# design.net
KiCad netlist of a schematic drawn in Altium Designer
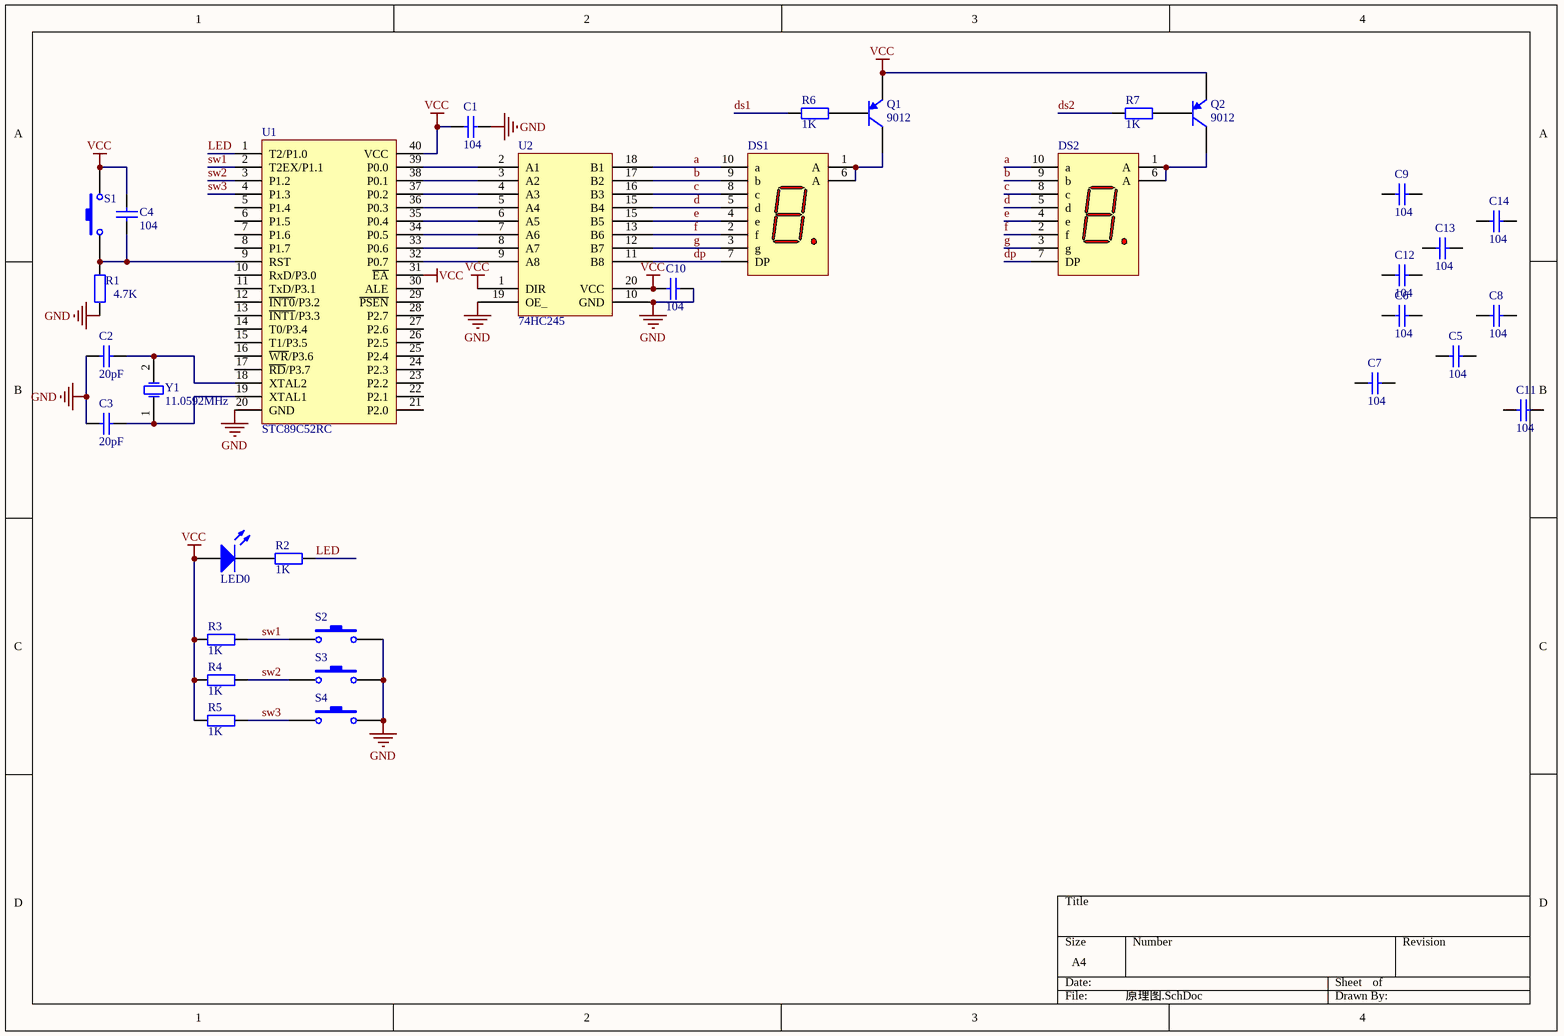
[diagram p0: 原理图.SchDoc]

(export (version "E")
  (design (tool "Eeschema 10.0.6"))
  (components
    (comp (ref "C1")
      (value "104")
      (footprint "RAD-0.3")
      (description "Capacitor")
      (fields (field (name "Comment") "Cap") (field (name "PUBLISHER") "Altium Limited"))
      (libsource (lib "Miscellaneous Devices") (part "Cap"))
    )
    (comp (ref "C2")
      (value "20pF")
      (footprint "RAD-0.3")
      (description "Capacitor")
      (fields (field (name "Comment") "Cap") (field (name "PUBLISHER") "Altium Limited"))
      (libsource (lib "Miscellaneous Devices") (part "Cap"))
    )
    (comp (ref "C3")
      (value "20pF")
      (footprint "RAD-0.3")
      (description "Capacitor")
      (fields (field (name "Comment") "Cap") (field (name "PUBLISHER") "Altium Limited"))
      (libsource (lib "Miscellaneous Devices") (part "Cap"))
    )
    (comp (ref "C4")
      (value "104")
      (footprint "RAD-0.3")
      (description "Capacitor")
      (fields (field (name "Comment") "Cap") (field (name "PUBLISHER") "Altium Limited"))
      (libsource (lib "Miscellaneous Devices") (part "Cap"))
    )
    (comp (ref "C5")
      (value "104")
      (footprint "RAD-0.3")
      (description "Capacitor")
      (fields (field (name "Comment") "Cap") (field (name "PUBLISHER") "Altium Limited"))
      (libsource (lib "Miscellaneous Devices") (part "Cap"))
    )
    (comp (ref "C6")
      (value "104")
      (footprint "RAD-0.3")
      (description "Capacitor")
      (fields (field (name "Comment") "Cap") (field (name "PUBLISHER") "Altium Limited"))
      (libsource (lib "Miscellaneous Devices") (part "Cap"))
    )
    (comp (ref "C7")
      (value "104")
      (footprint "RAD-0.3")
      (description "Capacitor")
      (fields (field (name "Comment") "Cap") (field (name "PUBLISHER") "Altium Limited"))
      (libsource (lib "Miscellaneous Devices") (part "Cap"))
    )
    (comp (ref "C8")
      (value "104")
      (footprint "RAD-0.3")
      (description "Capacitor")
      (fields (field (name "Comment") "Cap") (field (name "PUBLISHER") "Altium Limited"))
      (libsource (lib "Miscellaneous Devices") (part "Cap"))
    )
    (comp (ref "C9")
      (value "104")
      (footprint "RAD-0.3")
      (description "Capacitor")
      (fields (field (name "Comment") "Cap") (field (name "PUBLISHER") "Altium Limited"))
      (libsource (lib "Miscellaneous Devices") (part "Cap"))
    )
    (comp (ref "C10")
      (value "104")
      (footprint "RAD-0.3")
      (description "Capacitor")
      (fields (field (name "Comment") "Cap") (field (name "PUBLISHER") "Altium Limited"))
      (libsource (lib "Miscellaneous Devices") (part "Cap"))
    )
    (comp (ref "C11")
      (value "104")
      (footprint "RAD-0.3")
      (description "Capacitor")
      (fields (field (name "Comment") "Cap") (field (name "PUBLISHER") "Altium Limited"))
      (libsource (lib "Miscellaneous Devices") (part "Cap"))
    )
    (comp (ref "C12")
      (value "104")
      (footprint "RAD-0.3")
      (description "Capacitor")
      (fields (field (name "Comment") "Cap") (field (name "PUBLISHER") "Altium Limited"))
      (libsource (lib "Miscellaneous Devices") (part "Cap"))
    )
    (comp (ref "C13")
      (value "104")
      (footprint "RAD-0.3")
      (description "Capacitor")
      (fields (field (name "Comment") "Cap") (field (name "PUBLISHER") "Altium Limited"))
      (libsource (lib "Miscellaneous Devices") (part "Cap"))
    )
    (comp (ref "C14")
      (value "104")
      (footprint "RAD-0.3")
      (description "Capacitor")
      (fields (field (name "Comment") "Cap") (field (name "PUBLISHER") "Altium Limited"))
      (libsource (lib "Miscellaneous Devices") (part "Cap"))
    )
    (comp (ref "D1")
      (value "LED0")
      (footprint "LED-0")
      (description "Typical INFRARED GaAs LED")
      (fields (field (name "PUBLISHER") "Altium Limited"))
      (libsource (lib "Miscellaneous Devices") (part "LED0"))
    )
    (comp (ref "DS1")
      (value "Dpy Red-CA")
      (footprint "A")
      (description "7.62 mm Black Surface HER 7-Segment Display: CA, RH DP")
      (fields (field (name "PUBLISHER") "Altium Limited"))
      (libsource (lib "Miscellaneous Devices") (part "Dpy Red-CA"))
    )
    (comp (ref "DS2")
      (value "Dpy Red-CA")
      (footprint "A")
      (description "7.62 mm Black Surface HER 7-Segment Display: CA, RH DP")
      (fields (field (name "PUBLISHER") "Altium Limited"))
      (libsource (lib "Miscellaneous Devices") (part "Dpy Red-CA"))
    )
    (comp (ref "Q1")
      (value "9012")
      (footprint "SOT-23B_N")
      (description "PNP Bipolar Transistor")
      (fields (field (name "PUBLISHER") "Altium Limited"))
      (libsource (lib "Miscellaneous Devices") (part "PNP"))
    )
    (comp (ref "Q2")
      (value "9012")
      (footprint "SOT-23B_N")
      (description "PNP Bipolar Transistor")
      (fields (field (name "PUBLISHER") "Altium Limited"))
      (libsource (lib "Miscellaneous Devices") (part "PNP"))
    )
    (comp (ref "R1")
      (value "4.7K")
      (footprint "AXIAL-0.4")
      (description "Resistor")
      (fields (field (name "Comment") "Res2") (field (name "PUBLISHER") "Altium Limited"))
      (libsource (lib "") (part "Res2_1"))
    )
    (comp (ref "R2")
      (value "1K")
      (footprint "AXIAL-0.4")
      (description "Resistor")
      (fields (field (name "Comment") "Res2") (field (name "PUBLISHER") "Altium Limited"))
      (libsource (lib "Miscellaneous Devices") (part "Res2"))
    )
    (comp (ref "R3")
      (value "1K")
      (footprint "AXIAL-0.4")
      (description "Resistor")
      (fields (field (name "Comment") "Res2") (field (name "PUBLISHER") "Altium Limited"))
      (libsource (lib "Miscellaneous Devices") (part "Res2"))
    )
    (comp (ref "R4")
      (value "1K")
      (footprint "AXIAL-0.4")
      (description "Resistor")
      (fields (field (name "Comment") "Res2") (field (name "PUBLISHER") "Altium Limited"))
      (libsource (lib "Miscellaneous Devices") (part "Res2"))
    )
    (comp (ref "R5")
      (value "1K")
      (footprint "AXIAL-0.4")
      (description "Resistor")
      (fields (field (name "Comment") "Res2") (field (name "PUBLISHER") "Altium Limited"))
      (libsource (lib "Miscellaneous Devices") (part "Res2"))
    )
    (comp (ref "R6")
      (value "1K")
      (footprint "AXIAL-0.4")
      (description "Resistor")
      (fields (field (name "Comment") "Res2") (field (name "PUBLISHER") "Altium Limited"))
      (libsource (lib "Miscellaneous Devices") (part "Res2"))
    )
    (comp (ref "R7")
      (value "1K")
      (footprint "AXIAL-0.4")
      (description "Resistor")
      (fields (field (name "Comment") "Res2") (field (name "PUBLISHER") "Altium Limited"))
      (libsource (lib "Miscellaneous Devices") (part "Res2"))
    )
    (comp (ref "S1")
      (value "SW-PB")
      (footprint "SPST-2")
      (description "Switch")
      (fields (field (name "PUBLISHER") "Altium Limited"))
      (libsource (lib "Miscellaneous Devices") (part "SW-PB"))
    )
    (comp (ref "S2")
      (value "SW-PB")
      (footprint "SPST-2")
      (description "Switch")
      (fields (field (name "PUBLISHER") "Altium Limited"))
      (libsource (lib "Miscellaneous Devices") (part "SW-PB"))
    )
    (comp (ref "S3")
      (value "SW-PB")
      (footprint "SPST-2")
      (description "Switch")
      (fields (field (name "PUBLISHER") "Altium Limited"))
      (libsource (lib "Miscellaneous Devices") (part "SW-PB"))
    )
    (comp (ref "S4")
      (value "SW-PB")
      (footprint "SPST-2")
      (description "Switch")
      (fields (field (name "PUBLISHER") "Altium Limited"))
      (libsource (lib "Miscellaneous Devices") (part "SW-PB"))
    )
    (comp (ref "U1")
      (value "STC89C52RC")
      (footprint "DIP40-600")
      (description "STC单片机")
      (libsource (lib "2.3   - STC系列单片机") (part "STC89C52RC"))
    )
    (comp (ref "U2") (value "74HC245") (libsource (lib "1.2   - 74系列芯片") (part "74HC245")))
    (comp (ref "Y1")
      (value "11.0592MHz")
      (footprint "R38")
      (description "Crystal Oscillator")
      (fields (field (name "PUBLISHER") "Altium Limited"))
      (libsource (lib "Miscellaneous Devices") (part "XTAL"))
    )
  )
  (nets
    (net (code "1") (name "/LED") (class "Default")
      (node (ref "R2") (pin "2") (pinfunction "2_2") (pintype "passive"))
      (node (ref "U1") (pin "1") (pinfunction "T2/P1.0_1") (pintype "passive"))
    )
    (net (code "2") (name "/a") (class "Default")
      (node (ref "DS1") (pin "10") (pinfunction "a_10") (pintype "passive"))
      (node (ref "DS2") (pin "10") (pinfunction "a_10") (pintype "passive"))
      (node (ref "U2") (pin "18") (pinfunction "B1_18") (pintype "passive"))
    )
    (net (code "3") (name "/b") (class "Default")
      (node (ref "DS1") (pin "9") (pinfunction "b_9") (pintype "passive"))
      (node (ref "DS2") (pin "9") (pinfunction "b_9") (pintype "passive"))
      (node (ref "U2") (pin "17") (pinfunction "B2_17") (pintype "passive"))
    )
    (net (code "4") (name "/c") (class "Default")
      (node (ref "DS1") (pin "8") (pinfunction "c_8") (pintype "passive"))
      (node (ref "DS2") (pin "8") (pinfunction "c_8") (pintype "passive"))
      (node (ref "U2") (pin "16") (pinfunction "B3_16") (pintype "passive"))
    )
    (net (code "5") (name "/d") (class "Default")
      (node (ref "DS1") (pin "5") (pinfunction "d_5") (pintype "passive"))
      (node (ref "DS2") (pin "5") (pinfunction "d_5") (pintype "passive"))
      (node (ref "U2") (pin "15") (pinfunction "B4_15") (pintype "passive"))
    )
    (net (code "6") (name "/dp") (class "Default")
      (node (ref "DS1") (pin "7") (pinfunction "DP_7") (pintype "passive"))
      (node (ref "DS2") (pin "7") (pinfunction "DP_7") (pintype "passive"))
      (node (ref "U2") (pin "11") (pinfunction "B8_11") (pintype "passive"))
    )
    (net (code "7") (name "/ds1") (class "Default")
      (node (ref "R6") (pin "1") (pinfunction "1_1") (pintype "passive"))
    )
    (net (code "8") (name "/ds2") (class "Default")
      (node (ref "R7") (pin "1") (pinfunction "1_1") (pintype "passive"))
    )
    (net (code "9") (name "/e") (class "Default")
      (node (ref "DS1") (pin "4") (pinfunction "e_4") (pintype "passive"))
      (node (ref "DS2") (pin "4") (pinfunction "e_4") (pintype "passive"))
      (node (ref "U2") (pin "15") (pinfunction "B5_15") (pintype "passive"))
    )
    (net (code "10") (name "/f") (class "Default")
      (node (ref "DS1") (pin "2") (pinfunction "f_2") (pintype "passive"))
      (node (ref "DS2") (pin "2") (pinfunction "f_2") (pintype "passive"))
      (node (ref "U2") (pin "13") (pinfunction "B6_13") (pintype "passive"))
    )
    (net (code "11") (name "/g") (class "Default")
      (node (ref "DS1") (pin "3") (pinfunction "g_3") (pintype "passive"))
      (node (ref "DS2") (pin "3") (pinfunction "g_3") (pintype "passive"))
      (node (ref "U2") (pin "12") (pinfunction "B7_12") (pintype "passive"))
    )
    (net (code "12") (name "/sw1") (class "Default")
      (node (ref "R3") (pin "2") (pinfunction "2_2") (pintype "passive"))
      (node (ref "S2") (pin "1") (pinfunction "1_1") (pintype "passive"))
      (node (ref "U1") (pin "2") (pinfunction "T2EX/P1.1_2") (pintype "passive"))
    )
    (net (code "13") (name "/sw2") (class "Default")
      (node (ref "R4") (pin "2") (pinfunction "2_2") (pintype "passive"))
      (node (ref "S3") (pin "1") (pinfunction "1_1") (pintype "passive"))
      (node (ref "U1") (pin "3") (pinfunction "P1.2_3") (pintype "passive"))
    )
    (net (code "14") (name "/sw3") (class "Default")
      (node (ref "R5") (pin "2") (pinfunction "2_2") (pintype "passive"))
      (node (ref "S4") (pin "1") (pinfunction "1_1") (pintype "passive"))
      (node (ref "U1") (pin "4") (pinfunction "P1.3_4") (pintype "passive"))
    )
    (net (code "15") (name "GND") (class "Default")
      (node (ref "C1") (pin "2") (pinfunction "2_2") (pintype "passive"))
      (node (ref "C10") (pin "2") (pinfunction "2_2") (pintype "passive"))
      (node (ref "C2") (pin "1") (pinfunction "1_1") (pintype "passive"))
      (node (ref "C3") (pin "1") (pinfunction "1_1") (pintype "passive"))
      (node (ref "R1") (pin "1") (pinfunction "1_1") (pintype "passive"))
      (node (ref "S2") (pin "2") (pinfunction "2_2") (pintype "passive"))
      (node (ref "S3") (pin "2") (pinfunction "2_2") (pintype "passive"))
      (node (ref "S4") (pin "2") (pinfunction "2_2") (pintype "passive"))
      (node (ref "U1") (pin "20") (pinfunction "GND_20") (pintype "passive"))
      (node (ref "U2") (pin "10") (pinfunction "GND_10") (pintype "passive"))
      (node (ref "U2") (pin "19") (pinfunction "OE__19") (pintype "passive"))
    )
    (net (code "16") (name "Net-(D1-K)") (class "Default")
      (node (ref "D1") (pin "2") (pinfunction "K_2") (pintype "passive"))
      (node (ref "R2") (pin "1") (pinfunction "1_1") (pintype "passive"))
    )
    (net (code "17") (name "Net-(Q1-B)") (class "Default")
      (node (ref "Q1") (pin "2") (pinfunction "B_2") (pintype "passive"))
      (node (ref "R6") (pin "2") (pinfunction "2_2") (pintype "passive"))
    )
    (net (code "18") (name "Net-(Q1-C)") (class "Default")
      (node (ref "DS1") (pin "1") (pinfunction "A_1") (pintype "passive"))
      (node (ref "DS1") (pin "6") (pinfunction "A_6") (pintype "passive"))
      (node (ref "Q1") (pin "1") (pinfunction "C_1") (pintype "passive"))
    )
    (net (code "19") (name "Net-(Q2-B)") (class "Default")
      (node (ref "Q2") (pin "2") (pinfunction "B_2") (pintype "passive"))
      (node (ref "R7") (pin "2") (pinfunction "2_2") (pintype "passive"))
    )
    (net (code "20") (name "Net-(Q2-C)") (class "Default")
      (node (ref "DS2") (pin "1") (pinfunction "A_1") (pintype "passive"))
      (node (ref "DS2") (pin "6") (pinfunction "A_6") (pintype "passive"))
      (node (ref "Q2") (pin "1") (pinfunction "C_1") (pintype "passive"))
    )
    (net (code "21") (name "Net-(U1-P0.0)") (class "Default")
      (node (ref "U1") (pin "39") (pinfunction "P0.0_39") (pintype "passive"))
      (node (ref "U2") (pin "2") (pinfunction "A1_2") (pintype "passive"))
    )
    (net (code "22") (name "Net-(U1-P0.1)") (class "Default")
      (node (ref "U1") (pin "38") (pinfunction "P0.1_38") (pintype "passive"))
      (node (ref "U2") (pin "3") (pinfunction "A2_3") (pintype "passive"))
    )
    (net (code "23") (name "Net-(U1-P0.2)") (class "Default")
      (node (ref "U1") (pin "37") (pinfunction "P0.2_37") (pintype "passive"))
      (node (ref "U2") (pin "4") (pinfunction "A3_4") (pintype "passive"))
    )
    (net (code "24") (name "Net-(U1-P0.3)") (class "Default")
      (node (ref "U1") (pin "36") (pinfunction "P0.3_36") (pintype "passive"))
      (node (ref "U2") (pin "5") (pinfunction "A4_5") (pintype "passive"))
    )
    (net (code "25") (name "Net-(U1-P0.4)") (class "Default")
      (node (ref "U1") (pin "35") (pinfunction "P0.4_35") (pintype "passive"))
      (node (ref "U2") (pin "6") (pinfunction "A5_6") (pintype "passive"))
    )
    (net (code "26") (name "Net-(U1-P0.5)") (class "Default")
      (node (ref "U1") (pin "34") (pinfunction "P0.5_34") (pintype "passive"))
      (node (ref "U2") (pin "7") (pinfunction "A6_7") (pintype "passive"))
    )
    (net (code "27") (name "Net-(U1-P0.6)") (class "Default")
      (node (ref "U1") (pin "33") (pinfunction "P0.6_33") (pintype "passive"))
      (node (ref "U2") (pin "8") (pinfunction "A7_8") (pintype "passive"))
    )
    (net (code "28") (name "Net-(U1-P0.7)") (class "Default")
      (node (ref "U1") (pin "32") (pinfunction "P0.7_32") (pintype "passive"))
      (node (ref "U2") (pin "9") (pinfunction "A8_9") (pintype "passive"))
    )
    (net (code "29") (name "Net-(U1-RST)") (class "Default")
      (node (ref "C4") (pin "1") (pinfunction "1_1") (pintype "passive"))
      (node (ref "R1") (pin "2") (pinfunction "2_2") (pintype "passive"))
      (node (ref "S1") (pin "1") (pinfunction "1_1") (pintype "passive"))
      (node (ref "U1") (pin "9") (pinfunction "RST_9") (pintype "passive"))
    )
    (net (code "30") (name "Net-(U1-XTAL1)") (class "Default")
      (node (ref "C3") (pin "2") (pinfunction "2_2") (pintype "passive"))
      (node (ref "U1") (pin "19") (pinfunction "XTAL1_19") (pintype "passive"))
      (node (ref "Y1") (pin "1") (pinfunction "OSC1_1") (pintype "passive"))
    )
    (net (code "31") (name "Net-(U1-XTAL2)") (class "Default")
      (node (ref "C2") (pin "2") (pinfunction "2_2") (pintype "passive"))
      (node (ref "U1") (pin "18") (pinfunction "XTAL2_18") (pintype "passive"))
      (node (ref "Y1") (pin "2") (pinfunction "OSC2_2") (pintype "passive"))
    )
    (net (code "32") (name "VCC") (class "Default")
      (node (ref "C1") (pin "1") (pinfunction "1_1") (pintype "passive"))
      (node (ref "C10") (pin "1") (pinfunction "1_1") (pintype "passive"))
      (node (ref "C4") (pin "2") (pinfunction "2_2") (pintype "passive"))
      (node (ref "D1") (pin "1") (pinfunction "A_1") (pintype "passive"))
      (node (ref "Q1") (pin "3") (pinfunction "E_3") (pintype "passive"))
      (node (ref "Q2") (pin "3") (pinfunction "E_3") (pintype "passive"))
      (node (ref "R3") (pin "1") (pinfunction "1_1") (pintype "passive"))
      (node (ref "R4") (pin "1") (pinfunction "1_1") (pintype "passive"))
      (node (ref "R5") (pin "1") (pinfunction "1_1") (pintype "passive"))
      (node (ref "S1") (pin "2") (pinfunction "2_2") (pintype "passive"))
      (node (ref "U1") (pin "31") (pinfunction "~{EA}_31") (pintype "passive"))
      (node (ref "U1") (pin "40") (pinfunction "VCC_40") (pintype "passive"))
      (node (ref "U2") (pin "1") (pinfunction "DIR_1") (pintype "passive"))
      (node (ref "U2") (pin "20") (pinfunction "VCC_20") (pintype "passive"))
    )
    (net (code "33") (name "unconnected-(C5-Pad1)") (class "Default")
      (node (ref "C5") (pin "1") (pinfunction "1_1") (pintype "passive"))
    )
    (net (code "34") (name "unconnected-(C5-Pad2)") (class "Default")
      (node (ref "C5") (pin "2") (pinfunction "2_2") (pintype "passive"))
    )
    (net (code "35") (name "unconnected-(C6-Pad1)") (class "Default")
      (node (ref "C6") (pin "1") (pinfunction "1_1") (pintype "passive"))
    )
    (net (code "36") (name "unconnected-(C6-Pad2)") (class "Default")
      (node (ref "C6") (pin "2") (pinfunction "2_2") (pintype "passive"))
    )
    (net (code "37") (name "unconnected-(C7-Pad1)") (class "Default")
      (node (ref "C7") (pin "1") (pinfunction "1_1") (pintype "passive"))
    )
    (net (code "38") (name "unconnected-(C7-Pad2)") (class "Default")
      (node (ref "C7") (pin "2") (pinfunction "2_2") (pintype "passive"))
    )
    (net (code "39") (name "unconnected-(C8-Pad1)") (class "Default")
      (node (ref "C8") (pin "1") (pinfunction "1_1") (pintype "passive"))
    )
    (net (code "40") (name "unconnected-(C8-Pad2)") (class "Default")
      (node (ref "C8") (pin "2") (pinfunction "2_2") (pintype "passive"))
    )
    (net (code "41") (name "unconnected-(C9-Pad1)") (class "Default")
      (node (ref "C9") (pin "1") (pinfunction "1_1") (pintype "passive"))
    )
    (net (code "42") (name "unconnected-(C9-Pad2)") (class "Default")
      (node (ref "C9") (pin "2") (pinfunction "2_2") (pintype "passive"))
    )
    (net (code "43") (name "unconnected-(C11-Pad1)") (class "Default")
      (node (ref "C11") (pin "1") (pinfunction "1_1") (pintype "passive"))
    )
    (net (code "44") (name "unconnected-(C11-Pad2)") (class "Default")
      (node (ref "C11") (pin "2") (pinfunction "2_2") (pintype "passive"))
    )
    (net (code "45") (name "unconnected-(C12-Pad1)") (class "Default")
      (node (ref "C12") (pin "1") (pinfunction "1_1") (pintype "passive"))
    )
    (net (code "46") (name "unconnected-(C12-Pad2)") (class "Default")
      (node (ref "C12") (pin "2") (pinfunction "2_2") (pintype "passive"))
    )
    (net (code "47") (name "unconnected-(C13-Pad1)") (class "Default")
      (node (ref "C13") (pin "1") (pinfunction "1_1") (pintype "passive"))
    )
    (net (code "48") (name "unconnected-(C13-Pad2)") (class "Default")
      (node (ref "C13") (pin "2") (pinfunction "2_2") (pintype "passive"))
    )
    (net (code "49") (name "unconnected-(C14-Pad1)") (class "Default")
      (node (ref "C14") (pin "1") (pinfunction "1_1") (pintype "passive"))
    )
    (net (code "50") (name "unconnected-(C14-Pad2)") (class "Default")
      (node (ref "C14") (pin "2") (pinfunction "2_2") (pintype "passive"))
    )
    (net (code "51") (name "unconnected-(U1-ALE-Pad30)") (class "Default")
      (node (ref "U1") (pin "30") (pinfunction "ALE_30") (pintype "passive"))
    )
    (net (code "52") (name "unconnected-(U1-P1.4-Pad5)") (class "Default")
      (node (ref "U1") (pin "5") (pinfunction "P1.4_5") (pintype "passive"))
    )
    (net (code "53") (name "unconnected-(U1-P1.5-Pad6)") (class "Default")
      (node (ref "U1") (pin "6") (pinfunction "P1.5_6") (pintype "passive"))
    )
    (net (code "54") (name "unconnected-(U1-P1.6-Pad7)") (class "Default")
      (node (ref "U1") (pin "7") (pinfunction "P1.6_7") (pintype "passive"))
    )
    (net (code "55") (name "unconnected-(U1-P1.7-Pad8)") (class "Default")
      (node (ref "U1") (pin "8") (pinfunction "P1.7_8") (pintype "passive"))
    )
    (net (code "56") (name "unconnected-(U1-P2.0-Pad21)") (class "Default")
      (node (ref "U1") (pin "21") (pinfunction "P2.0_21") (pintype "passive"))
    )
    (net (code "57") (name "unconnected-(U1-P2.1-Pad22)") (class "Default")
      (node (ref "U1") (pin "22") (pinfunction "P2.1_22") (pintype "passive"))
    )
    (net (code "58") (name "unconnected-(U1-P2.2-Pad23)") (class "Default")
      (node (ref "U1") (pin "23") (pinfunction "P2.2_23") (pintype "passive"))
    )
    (net (code "59") (name "unconnected-(U1-P2.3-Pad24)") (class "Default")
      (node (ref "U1") (pin "24") (pinfunction "P2.3_24") (pintype "passive"))
    )
    (net (code "60") (name "unconnected-(U1-P2.4-Pad25)") (class "Default")
      (node (ref "U1") (pin "25") (pinfunction "P2.4_25") (pintype "passive"))
    )
    (net (code "61") (name "unconnected-(U1-P2.5-Pad26)") (class "Default")
      (node (ref "U1") (pin "26") (pinfunction "P2.5_26") (pintype "passive"))
    )
    (net (code "62") (name "unconnected-(U1-P2.6-Pad27)") (class "Default")
      (node (ref "U1") (pin "27") (pinfunction "P2.6_27") (pintype "passive"))
    )
    (net (code "63") (name "unconnected-(U1-P2.7-Pad28)") (class "Default")
      (node (ref "U1") (pin "28") (pinfunction "P2.7_28") (pintype "passive"))
    )
    (net (code "64") (name "unconnected-(U1-RxD{slash}P3.0-Pad10)") (class "Default")
      (node (ref "U1") (pin "10") (pinfunction "RxD/P3.0_10") (pintype "passive"))
    )
    (net (code "65") (name "unconnected-(U1-T0{slash}P3.4-Pad14)") (class "Default")
      (node (ref "U1") (pin "14") (pinfunction "T0/P3.4_14") (pintype "passive"))
    )
    (net (code "66") (name "unconnected-(U1-T1{slash}P3.5-Pad15)") (class "Default")
      (node (ref "U1") (pin "15") (pinfunction "T1/P3.5_15") (pintype "passive"))
    )
    (net (code "67") (name "unconnected-(U1-TxD{slash}P3.1-Pad11)") (class "Default")
      (node (ref "U1") (pin "11") (pinfunction "TxD/P3.1_11") (pintype "passive"))
    )
    (net (code "68") (name "unconnected-(U1-~{INT0}{slash}P3.2-Pad12)") (class "Default")
      (node (ref "U1") (pin "12") (pinfunction "~{INT0}/P3.2_12") (pintype "passive"))
    )
    (net (code "69") (name "unconnected-(U1-~{INT1}{slash}P3.3-Pad13)") (class "Default")
      (node (ref "U1") (pin "13") (pinfunction "~{INT1}/P3.3_13") (pintype "passive"))
    )
    (net (code "70") (name "unconnected-(U1-~{PSEN}-Pad29)") (class "Default")
      (node (ref "U1") (pin "29") (pinfunction "~{PSEN}_29") (pintype "passive"))
    )
    (net (code "71") (name "unconnected-(U1-~{RD}{slash}P3.7-Pad17)") (class "Default")
      (node (ref "U1") (pin "17") (pinfunction "~{RD}/P3.7_17") (pintype "passive"))
    )
    (net (code "72") (name "unconnected-(U1-~{WR}{slash}P3.6-Pad16)") (class "Default")
      (node (ref "U1") (pin "16") (pinfunction "~{WR}/P3.6_16") (pintype "passive"))
    )
  )
)
